# Front_panel_owon_ver_mini.net
KiCad netlist of a schematic drawn in EAGLE
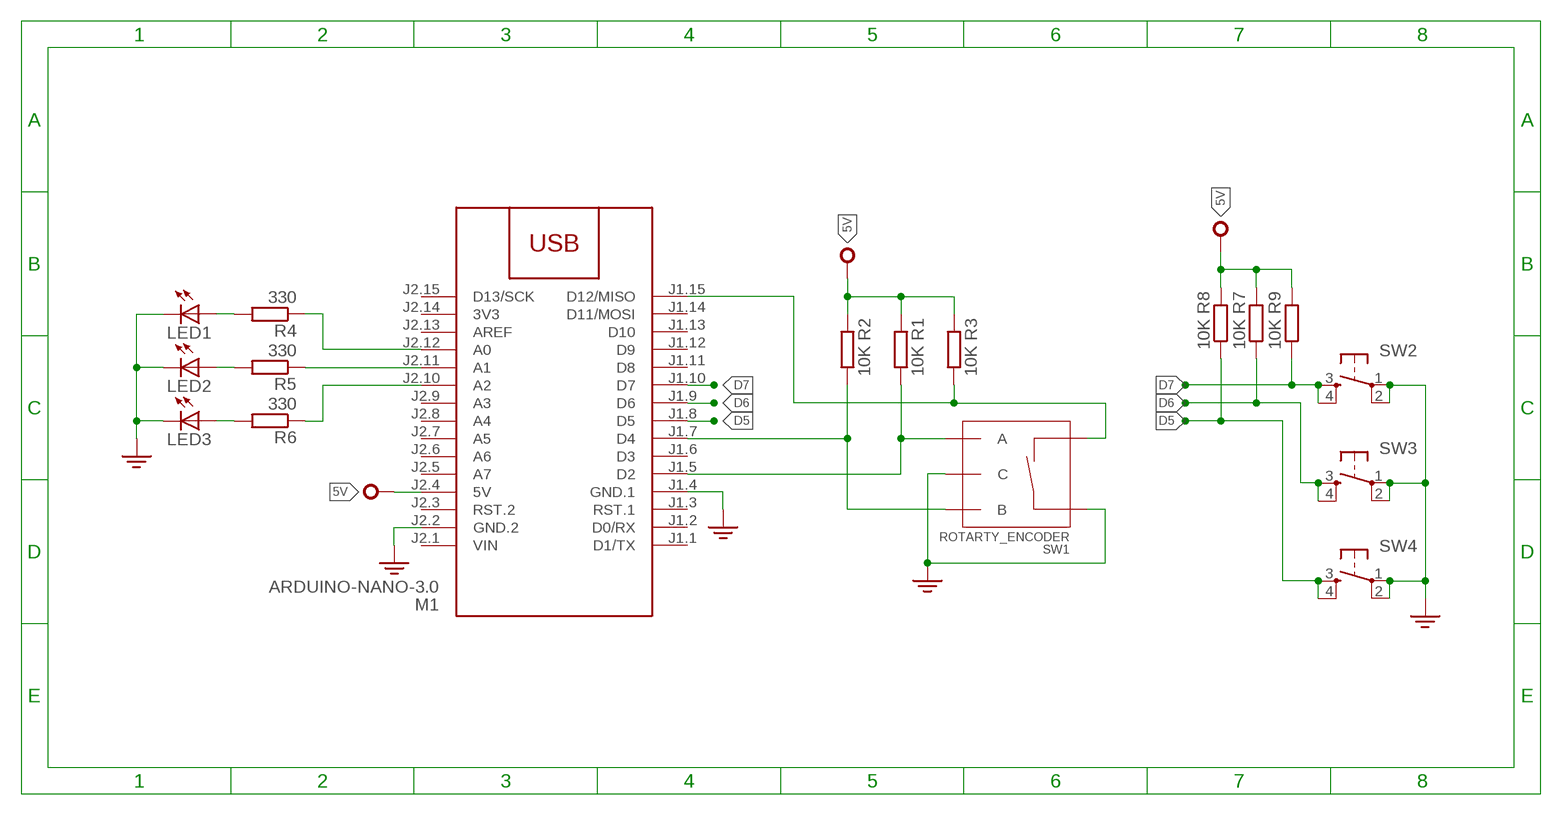
[diagram p0: schematic, sheet 1]

(export (version "E")
  (design (tool "Eeschema 10.0.6"))
  (components
    (comp (ref "LED1")
      (value "LED5MM")
      (footprint "eagle-import:LED5MM")
      (libsource (lib "eagle-import") (part "LED5MM"))
    )
    (comp (ref "LED2")
      (value "LED5MM")
      (footprint "eagle-import:LED5MM")
      (libsource (lib "eagle-import") (part "LED5MM"))
    )
    (comp (ref "LED3")
      (value "LED5MM")
      (footprint "eagle-import:LED5MM")
      (libsource (lib "eagle-import") (part "LED5MM"))
    )
    (comp (ref "M1")
      (value "ARDUINO-NANO-3.0")
      (footprint "eagle-import:ARDUINO-NANO-3.0")
      (libsource (lib "eagle-import") (part "ARDUINO-NANO-3.0"))
    )
    (comp (ref "R1")
      (value "10K")
      (footprint "eagle-import:0204_7")
      (libsource (lib "eagle-import") (part "R-EU_0204/7"))
    )
    (comp (ref "R2")
      (value "10K")
      (footprint "eagle-import:0204_7")
      (libsource (lib "eagle-import") (part "R-EU_0204/7"))
    )
    (comp (ref "R3")
      (value "10K")
      (footprint "eagle-import:0204_7")
      (libsource (lib "eagle-import") (part "R-EU_0204/7"))
    )
    (comp (ref "R4")
      (value "330")
      (footprint "eagle-import:0204_7")
      (libsource (lib "eagle-import") (part "R-EU_0204/7"))
    )
    (comp (ref "R5")
      (value "330")
      (footprint "eagle-import:0204_7")
      (libsource (lib "eagle-import") (part "R-EU_0204/7"))
    )
    (comp (ref "R6")
      (value "330")
      (footprint "eagle-import:0204_7")
      (libsource (lib "eagle-import") (part "R-EU_0204/7"))
    )
    (comp (ref "R7")
      (value "10K")
      (footprint "eagle-import:0204_7")
      (libsource (lib "eagle-import") (part "R-EU_0204/7"))
    )
    (comp (ref "R8")
      (value "10K")
      (footprint "eagle-import:0204_7")
      (libsource (lib "eagle-import") (part "R-EU_0204/7"))
    )
    (comp (ref "R9")
      (value "10K")
      (footprint "eagle-import:0204_7")
      (libsource (lib "eagle-import") (part "R-EU_0204/7"))
    )
    (comp (ref "SW1")
      (value "ROTARTY_ENCODER")
      (footprint "eagle-import:ROTARY_ENC_PLAIN")
      (libsource (lib "eagle-import") (part "ROTARTY_ENCODER"))
    )
    (comp (ref "SW2")
      (value "TACTILE-SWITCH-PTH")
      (footprint "eagle-import:TAC-SWITCH-PTH")
      (libsource (lib "eagle-import") (part "TACTILE-SWITCH-PTH"))
    )
    (comp (ref "SW3")
      (value "TACTILE-SWITCH-PTH")
      (footprint "eagle-import:TAC-SWITCH-PTH")
      (libsource (lib "eagle-import") (part "TACTILE-SWITCH-PTH"))
    )
    (comp (ref "SW4")
      (value "TACTILE-SWITCH-PTH")
      (footprint "eagle-import:TAC-SWITCH-PTH")
      (libsource (lib "eagle-import") (part "TACTILE-SWITCH-PTH"))
    )
  )
  (nets
    (net (code "1") (name "/3V3") (class "Default")
      (node (ref "M1") (pin "J2.14") (pinfunction "3V3_J2.14") (pintype "power_in"))
    )
    (net (code "2") (name "/VIN") (class "Default")
      (node (ref "M1") (pin "J2.1") (pinfunction "VIN_J2.1") (pintype "power_in"))
    )
    (net (code "3") (name "5V") (class "Default")
      (node (ref "M1") (pin "J2.4") (pinfunction "5V_J2.4") (pintype "power_in"))
      (node (ref "R1") (pin "2") (pinfunction "2_2") (pintype "passive"))
      (node (ref "R2") (pin "2") (pinfunction "2_2") (pintype "passive"))
      (node (ref "R3") (pin "2") (pinfunction "2_2") (pintype "passive"))
      (node (ref "R7") (pin "2") (pinfunction "2_2") (pintype "passive"))
      (node (ref "R8") (pin "2") (pinfunction "2_2") (pintype "passive"))
      (node (ref "R9") (pin "2") (pinfunction "2_2") (pintype "passive"))
    )
    (net (code "4") (name "D5") (class "Default")
      (node (ref "M1") (pin "J1.8") (pinfunction "D5_J1.8") (pintype "bidirectional"))
      (node (ref "R8") (pin "1") (pinfunction "1_1") (pintype "passive"))
      (node (ref "SW4") (pin "3") (pinfunction "3_3") (pintype "passive"))
      (node (ref "SW4") (pin "4") (pinfunction "4_4") (pintype "passive"))
    )
    (net (code "5") (name "D6") (class "Default")
      (node (ref "M1") (pin "J1.9") (pinfunction "D6_J1.9") (pintype "bidirectional"))
      (node (ref "R7") (pin "1") (pinfunction "1_1") (pintype "passive"))
      (node (ref "SW3") (pin "3") (pinfunction "3_3") (pintype "passive"))
      (node (ref "SW3") (pin "4") (pinfunction "4_4") (pintype "passive"))
    )
    (net (code "6") (name "D7") (class "Default")
      (node (ref "M1") (pin "J1.10") (pinfunction "D7_J1.10") (pintype "bidirectional"))
      (node (ref "R9") (pin "1") (pinfunction "1_1") (pintype "passive"))
      (node (ref "SW2") (pin "3") (pinfunction "3_3") (pintype "passive"))
      (node (ref "SW2") (pin "4") (pinfunction "4_4") (pintype "passive"))
    )
    (net (code "7") (name "GND2") (class "Default")
      (node (ref "LED1") (pin "K") (pinfunction "C_K") (pintype "passive"))
      (node (ref "LED2") (pin "K") (pinfunction "C_K") (pintype "passive"))
      (node (ref "LED3") (pin "K") (pinfunction "C_K") (pintype "passive"))
      (node (ref "M1") (pin "J1.4") (pinfunction "GND.1_J1.4") (pintype "power_in"))
      (node (ref "M1") (pin "J2.2") (pinfunction "GND.2_J2.2") (pintype "power_in"))
      (node (ref "SW1") (pin "C") (pinfunction "C_C") (pintype "bidirectional"))
      (node (ref "SW1") (pin "SW+") (pinfunction "SW+_SW+") (pintype "bidirectional"))
      (node (ref "SW2") (pin "1") (pinfunction "1_1") (pintype "passive"))
      (node (ref "SW2") (pin "2") (pinfunction "2_2") (pintype "passive"))
      (node (ref "SW3") (pin "1") (pinfunction "1_1") (pintype "passive"))
      (node (ref "SW3") (pin "2") (pinfunction "2_2") (pintype "passive"))
      (node (ref "SW4") (pin "1") (pinfunction "1_1") (pintype "passive"))
      (node (ref "SW4") (pin "2") (pinfunction "2_2") (pintype "passive"))
    )
    (net (code "8") (name "Net-(LED1-PadA)") (class "Default")
      (node (ref "LED1") (pin "A") (pinfunction "A_A") (pintype "passive"))
      (node (ref "R4") (pin "2") (pinfunction "2_2") (pintype "passive"))
    )
    (net (code "9") (name "Net-(LED2-PadA)") (class "Default")
      (node (ref "LED2") (pin "A") (pinfunction "A_A") (pintype "passive"))
      (node (ref "R5") (pin "2") (pinfunction "2_2") (pintype "passive"))
    )
    (net (code "10") (name "Net-(LED3-PadA)") (class "Default")
      (node (ref "LED3") (pin "A") (pinfunction "A_A") (pintype "passive"))
      (node (ref "R6") (pin "2") (pinfunction "2_2") (pintype "passive"))
    )
    (net (code "11") (name "Net-(M1-A0)") (class "Default")
      (node (ref "M1") (pin "J2.12") (pinfunction "A0_J2.12") (pintype "bidirectional"))
      (node (ref "R4") (pin "1") (pinfunction "1_1") (pintype "passive"))
    )
    (net (code "12") (name "Net-(M1-A1)") (class "Default")
      (node (ref "M1") (pin "J2.11") (pinfunction "A1_J2.11") (pintype "bidirectional"))
      (node (ref "R5") (pin "1") (pinfunction "1_1") (pintype "passive"))
    )
    (net (code "13") (name "Net-(M1-A2)") (class "Default")
      (node (ref "M1") (pin "J2.10") (pinfunction "A2_J2.10") (pintype "bidirectional"))
      (node (ref "R6") (pin "1") (pinfunction "1_1") (pintype "passive"))
    )
    (net (code "14") (name "Net-(M1-D2)") (class "Default")
      (node (ref "M1") (pin "J1.5") (pinfunction "D2_J1.5") (pintype "bidirectional"))
      (node (ref "R1") (pin "1") (pinfunction "1_1") (pintype "passive"))
      (node (ref "SW1") (pin "A") (pinfunction "A_A") (pintype "bidirectional"))
    )
    (net (code "15") (name "Net-(M1-D4)") (class "Default")
      (node (ref "M1") (pin "J1.7") (pinfunction "D4_J1.7") (pintype "bidirectional"))
      (node (ref "R2") (pin "1") (pinfunction "1_1") (pintype "passive"))
      (node (ref "SW1") (pin "B") (pinfunction "B_B") (pintype "bidirectional"))
    )
    (net (code "16") (name "Net-(M1-D12{slash}MISO)") (class "Default")
      (node (ref "M1") (pin "J1.15") (pinfunction "D12/MISO_J1.15") (pintype "bidirectional"))
      (node (ref "R3") (pin "1") (pinfunction "1_1") (pintype "passive"))
      (node (ref "SW1") (pin "SW-") (pinfunction "SW-_SW-") (pintype "bidirectional"))
    )
    (net (code "17") (name "unconnected-(M1-A3-PadJ2.9)") (class "Default")
      (node (ref "M1") (pin "J2.9") (pinfunction "A3_J2.9") (pintype "bidirectional"))
    )
    (net (code "18") (name "unconnected-(M1-A4-PadJ2.8)") (class "Default")
      (node (ref "M1") (pin "J2.8") (pinfunction "A4_J2.8") (pintype "bidirectional"))
    )
    (net (code "19") (name "unconnected-(M1-A5-PadJ2.7)") (class "Default")
      (node (ref "M1") (pin "J2.7") (pinfunction "A5_J2.7") (pintype "bidirectional"))
    )
    (net (code "20") (name "unconnected-(M1-A6-PadJ2.6)") (class "Default")
      (node (ref "M1") (pin "J2.6") (pinfunction "A6_J2.6") (pintype "bidirectional"))
    )
    (net (code "21") (name "unconnected-(M1-A7-PadJ2.5)") (class "Default")
      (node (ref "M1") (pin "J2.5") (pinfunction "A7_J2.5") (pintype "bidirectional"))
    )
    (net (code "22") (name "unconnected-(M1-AREF-PadJ2.13)") (class "Default")
      (node (ref "M1") (pin "J2.13") (pinfunction "AREF_J2.13") (pintype "bidirectional"))
    )
    (net (code "23") (name "unconnected-(M1-D0{slash}RX-PadJ1.2)") (class "Default")
      (node (ref "M1") (pin "J1.2") (pinfunction "D0/RX_J1.2") (pintype "bidirectional"))
    )
    (net (code "24") (name "unconnected-(M1-D1{slash}TX-PadJ1.1)") (class "Default")
      (node (ref "M1") (pin "J1.1") (pinfunction "D1/TX_J1.1") (pintype "bidirectional"))
    )
    (net (code "25") (name "unconnected-(M1-D3-PadJ1.6)") (class "Default")
      (node (ref "M1") (pin "J1.6") (pinfunction "D3_J1.6") (pintype "bidirectional"))
    )
    (net (code "26") (name "unconnected-(M1-D8-PadJ1.11)") (class "Default")
      (node (ref "M1") (pin "J1.11") (pinfunction "D8_J1.11") (pintype "bidirectional"))
    )
    (net (code "27") (name "unconnected-(M1-D9-PadJ1.12)") (class "Default")
      (node (ref "M1") (pin "J1.12") (pinfunction "D9_J1.12") (pintype "bidirectional"))
    )
    (net (code "28") (name "unconnected-(M1-D10-PadJ1.13)") (class "Default")
      (node (ref "M1") (pin "J1.13") (pinfunction "D10_J1.13") (pintype "bidirectional"))
    )
    (net (code "29") (name "unconnected-(M1-D11{slash}MOSI-PadJ1.14)") (class "Default")
      (node (ref "M1") (pin "J1.14") (pinfunction "D11/MOSI_J1.14") (pintype "bidirectional"))
    )
    (net (code "30") (name "unconnected-(M1-D13{slash}SCK-PadJ2.15)") (class "Default")
      (node (ref "M1") (pin "J2.15") (pinfunction "D13/SCK_J2.15") (pintype "bidirectional"))
    )
    (net (code "31") (name "unconnected-(M1-RST.1-PadJ1.3)") (class "Default")
      (node (ref "M1") (pin "J1.3") (pinfunction "RST.1_J1.3") (pintype "bidirectional"))
    )
    (net (code "32") (name "unconnected-(M1-RST.2-PadJ2.3)") (class "Default")
      (node (ref "M1") (pin "J2.3") (pinfunction "RST.2_J2.3") (pintype "bidirectional"))
    )
  )
)
